# 01_Power_IN.net
KiCad netlist of a schematic drawn in Altium Designer
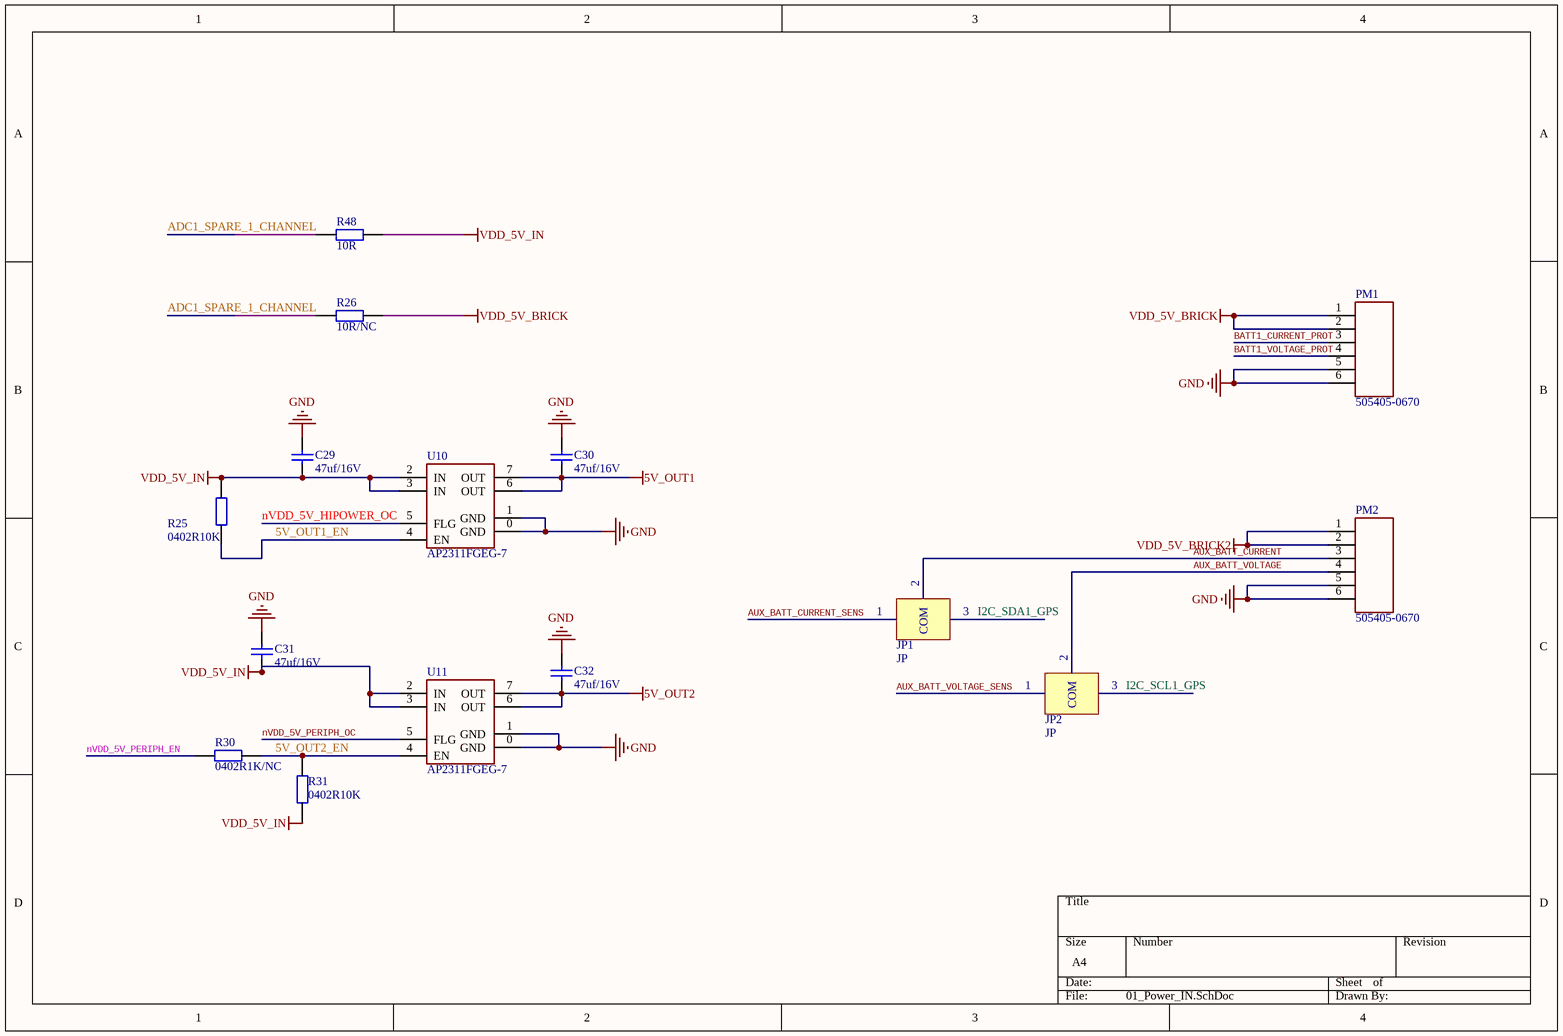
[diagram p0: 01_Power_IN.SchDoc]

(export (version "E")
  (design (tool "Eeschema 10.0.6"))
  (components
    (comp (ref "C29")
      (value "47uf/16V")
      (description "Capacitor")
      (libsource (lib "Miscellaneous Devices") (part "Cap"))
    )
    (comp (ref "C30")
      (value "47uf/16V")
      (description "Capacitor")
      (libsource (lib "Miscellaneous Devices") (part "Cap"))
    )
    (comp (ref "C31")
      (value "47uf/16V")
      (description "Capacitor")
      (libsource (lib "Miscellaneous Devices") (part "Cap"))
    )
    (comp (ref "C32")
      (value "47uf/16V")
      (description "Capacitor")
      (libsource (lib "Miscellaneous Devices") (part "Cap"))
    )
    (comp (ref "JP1") (value "JP") (footprint "0402R-SR") (libsource (lib "CUAV") (part "0402R-SR")))
    (comp (ref "JP2") (value "JP") (footprint "0402R-SR") (libsource (lib "CUAV") (part "0402R-SR")))
    (comp (ref "PM1")
      (value "505405-0670")
      (footprint "5054050660")
      (libsource (lib "CUAV") (part "5054050660"))
    )
    (comp (ref "PM2")
      (value "505405-0670")
      (footprint "5054050660")
      (libsource (lib "CUAV") (part "5054050660"))
    )
    (comp (ref "R25")
      (value "0402R10K")
      (footprint "0402R")
      (description "0402R1K 1%")
      (libsource (lib "CUAV") (part "0402R1K"))
    )
    (comp (ref "R26")
      (value "10R/NC")
      (footprint "0402R")
      (description "0402R1K 1%")
      (libsource (lib "") (part "0402R1K_1"))
    )
    (comp (ref "R30")
      (value "0402R1K/NC")
      (footprint "0402R")
      (description "0402R1K 1%")
      (libsource (lib "") (part "0402R1K_3"))
    )
    (comp (ref "R31")
      (value "0402R10K")
      (footprint "0402R")
      (description "0402R1K 1%")
      (libsource (lib "") (part "0402R1K_2"))
    )
    (comp (ref "R48")
      (value "10R")
      (footprint "0402R")
      (description "0402R1K 1%")
      (libsource (lib "") (part "0402R1K_1"))
    )
    (comp (ref "U10")
      (value "AP2311FGEG-7")
      (footprint "QFN8_0.65")
      (libsource (lib "CUAV") (part "AP2311FGEG-7"))
    )
    (comp (ref "U11")
      (value "AP2311FGEG-7")
      (footprint "QFN8_0.65")
      (libsource (lib "CUAV") (part "AP2311FGEG-7"))
    )
  )
  (nets
    (net (code "1") (name "/5V_OUT1_EN") (class "Default")
      (node (ref "R25") (pin "1") (pintype "passive"))
      (node (ref "U10") (pin "4") (pinfunction "EN_4") (pintype "passive"))
    )
    (net (code "2") (name "/5V_OUT2_EN") (class "Default")
      (node (ref "R30") (pin "1") (pintype "passive"))
      (node (ref "R31") (pin "1") (pintype "passive"))
      (node (ref "U11") (pin "4") (pinfunction "EN_4") (pintype "passive"))
    )
    (net (code "3") (name "/ADC1_SPARE_1_CHANNEL") (class "Default")
      (node (ref "R26") (pin "1") (pintype "passive"))
      (node (ref "R48") (pin "1") (pintype "passive"))
    )
    (net (code "4") (name "/AUX_BATT_CURRENT") (class "Default")
      (node (ref "JP1") (pin "2") (pinfunction "COM_2") (pintype "passive"))
      (node (ref "PM2") (pin "3") (pintype "passive"))
    )
    (net (code "5") (name "/AUX_BATT_CURRENT_SENS") (class "Default")
      (node (ref "JP1") (pin "1") (pintype "passive"))
    )
    (net (code "6") (name "/AUX_BATT_VOLTAGE") (class "Default")
      (node (ref "JP2") (pin "2") (pinfunction "COM_2") (pintype "passive"))
      (node (ref "PM2") (pin "4") (pintype "passive"))
    )
    (net (code "7") (name "/AUX_BATT_VOLTAGE_SENS") (class "Default")
      (node (ref "JP2") (pin "1") (pintype "passive"))
    )
    (net (code "8") (name "/BATT1_CURRENT_PROT") (class "Default")
      (node (ref "PM1") (pin "3") (pintype "passive"))
    )
    (net (code "9") (name "/BATT1_VOLTAGE_PROT") (class "Default")
      (node (ref "PM1") (pin "4") (pintype "passive"))
    )
    (net (code "10") (name "/I2C_SCL1_GPS") (class "Default")
      (node (ref "JP2") (pin "3") (pintype "passive"))
    )
    (net (code "11") (name "/I2C_SDA1_GPS") (class "Default")
      (node (ref "JP1") (pin "3") (pintype "passive"))
    )
    (net (code "12") (name "/nVDD_5V_HIPOWER_OC") (class "Default")
      (node (ref "U10") (pin "5") (pinfunction "FLG_5") (pintype "passive"))
    )
    (net (code "13") (name "/nVDD_5V_PERIPH_EN") (class "Default")
      (node (ref "R30") (pin "2") (pintype "passive"))
    )
    (net (code "14") (name "/nVDD_5V_PERIPH_OC") (class "Default")
      (node (ref "U11") (pin "5") (pinfunction "FLG_5") (pintype "passive"))
    )
    (net (code "15") (name "5V_OUT1") (class "Default")
      (node (ref "C30") (pin "1") (pinfunction "1_1") (pintype "passive"))
      (node (ref "U10") (pin "6") (pinfunction "OUT_6") (pintype "passive"))
      (node (ref "U10") (pin "7") (pinfunction "OUT_7") (pintype "passive"))
    )
    (net (code "16") (name "5V_OUT2") (class "Default")
      (node (ref "C32") (pin "1") (pinfunction "1_1") (pintype "passive"))
      (node (ref "U11") (pin "6") (pinfunction "OUT_6") (pintype "passive"))
      (node (ref "U11") (pin "7") (pinfunction "OUT_7") (pintype "passive"))
    )
    (net (code "17") (name "GND") (class "Default")
      (node (ref "C29") (pin "2") (pinfunction "2_2") (pintype "passive"))
      (node (ref "C30") (pin "2") (pinfunction "2_2") (pintype "passive"))
      (node (ref "C31") (pin "2") (pinfunction "2_2") (pintype "passive"))
      (node (ref "C32") (pin "2") (pinfunction "2_2") (pintype "passive"))
      (node (ref "PM1") (pin "5") (pintype "passive"))
      (node (ref "PM1") (pin "6") (pintype "passive"))
      (node (ref "PM2") (pin "5") (pintype "passive"))
      (node (ref "PM2") (pin "6") (pintype "passive"))
      (node (ref "U10") (pin "0") (pinfunction "GND_0") (pintype "passive"))
      (node (ref "U10") (pin "1") (pinfunction "GND_1") (pintype "passive"))
      (node (ref "U11") (pin "0") (pinfunction "GND_0") (pintype "passive"))
      (node (ref "U11") (pin "1") (pinfunction "GND_1") (pintype "passive"))
    )
    (net (code "18") (name "VDD_5V_BRICK") (class "Default")
      (node (ref "PM1") (pin "1") (pintype "passive"))
      (node (ref "PM1") (pin "2") (pintype "passive"))
      (node (ref "R26") (pin "2") (pintype "passive"))
    )
    (net (code "19") (name "VDD_5V_BRICK2") (class "Default")
      (node (ref "PM2") (pin "1") (pintype "passive"))
      (node (ref "PM2") (pin "2") (pintype "passive"))
    )
    (net (code "20") (name "VDD_5V_IN") (class "Default")
      (node (ref "C29") (pin "1") (pinfunction "1_1") (pintype "passive"))
      (node (ref "C31") (pin "1") (pinfunction "1_1") (pintype "passive"))
      (node (ref "R25") (pin "2") (pintype "passive"))
      (node (ref "R31") (pin "2") (pintype "passive"))
      (node (ref "R48") (pin "2") (pintype "passive"))
      (node (ref "U10") (pin "2") (pinfunction "IN_2") (pintype "passive"))
      (node (ref "U10") (pin "3") (pinfunction "IN_3") (pintype "passive"))
      (node (ref "U11") (pin "2") (pinfunction "IN_2") (pintype "passive"))
      (node (ref "U11") (pin "3") (pinfunction "IN_3") (pintype "passive"))
    )
  )
)
